# sensors.net
KiCad netlist of a schematic drawn in Altium Designer
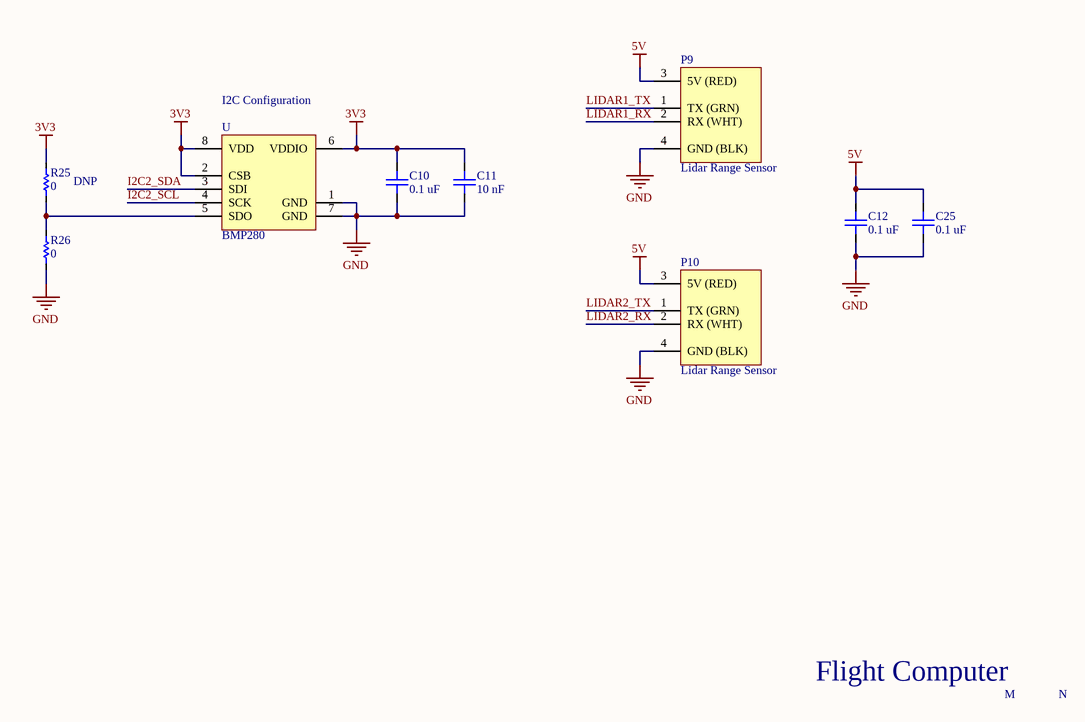
[diagram p0: sensors.SchDoc]

(export (version "E")
  (design (tool "Eeschema 10.0.6"))
  (components
    (comp (ref "C10")
      (value "0.1 uF")
      (footprint "CAP-CER-0805-SHORT")
      (description "±10%, 0805")
      (libsource (lib "passive") (part "CAP-CER-0.1uF-25V"))
    )
    (comp (ref "C11")
      (value "10 nF")
      (footprint "CAP-CER-0805-SHORT")
      (description "±10%, 0805")
      (libsource (lib "passive") (part "CAP-CER-10nF-50V"))
    )
    (comp (ref "C12")
      (value "0.1 uF")
      (footprint "CAP-CER-0805-SHORT")
      (description "±10%, 0805")
      (libsource (lib "passive") (part "CAP-CER-0.1uF-25V"))
    )
    (comp (ref "C25")
      (value "0.1 uF")
      (footprint "CAP-CER-0805-SHORT")
      (description "±10%, 0805")
      (libsource (lib "passive") (part "CAP-CER-0.1uF-25V"))
    )
    (comp (ref "P9")
      (value "Lidar Range Sensor")
      (footprint "4x1 Shrouded Header 1.25mm")
      (libsource (lib "connector") (part "Lidar Range Sensor"))
    )
    (comp (ref "P10")
      (value "Lidar Range Sensor")
      (footprint "4x1 Shrouded Header 1.25mm")
      (libsource (lib "connector") (part "Lidar Range Sensor"))
    )
    (comp (ref "R25")
      (value "0")
      (footprint "RES-0805")
      (description "0805")
      (libsource (lib "passive") (part "RES-0-1/8W"))
    )
    (comp (ref "R26")
      (value "0")
      (footprint "RES-0805")
      (description "0805")
      (libsource (lib "passive") (part "RES-0-1/8W"))
    )
    (comp (ref "U")
      (value "BMP280")
      (footprint "LGA8")
      (description "Digital Pressure Sensor")
      (libsource (lib "ic") (part "BMP280"))
    )
  )
  (nets
    (net (code "1") (name "/I2C2_SCL") (class "Default")
      (node (ref "U") (pin "4") (pinfunction "SCK_4") (pintype "passive"))
    )
    (net (code "2") (name "/I2C2_SDA") (class "Default")
      (node (ref "U") (pin "3") (pinfunction "SDI_3") (pintype "passive"))
    )
    (net (code "3") (name "/LIDAR1_RX") (class "Default")
      (node (ref "P9") (pin "2") (pinfunction "RX_(WHT)_2") (pintype "passive"))
    )
    (net (code "4") (name "/LIDAR1_TX") (class "Default")
      (node (ref "P9") (pin "1") (pinfunction "TX_(GRN)_1") (pintype "passive"))
    )
    (net (code "5") (name "/LIDAR2_RX") (class "Default")
      (node (ref "P10") (pin "2") (pinfunction "RX_(WHT)_2") (pintype "passive"))
    )
    (net (code "6") (name "/LIDAR2_TX") (class "Default")
      (node (ref "P10") (pin "1") (pinfunction "TX_(GRN)_1") (pintype "passive"))
    )
    (net (code "7") (name "3V3") (class "Default")
      (node (ref "C10") (pin "2") (pinfunction "2_2") (pintype "passive"))
      (node (ref "C11") (pin "2") (pinfunction "2_2") (pintype "passive"))
      (node (ref "R25") (pin "2") (pinfunction "2_2") (pintype "passive"))
      (node (ref "U") (pin "2") (pinfunction "CSB_2") (pintype "passive"))
      (node (ref "U") (pin "6") (pinfunction "VDDIO_6") (pintype "passive"))
      (node (ref "U") (pin "8") (pinfunction "VDD_8") (pintype "passive"))
    )
    (net (code "8") (name "5V") (class "Default")
      (node (ref "C12") (pin "2") (pinfunction "2_2") (pintype "passive"))
      (node (ref "C25") (pin "2") (pinfunction "2_2") (pintype "passive"))
      (node (ref "P10") (pin "3") (pinfunction "5V_(RED)_3") (pintype "passive"))
      (node (ref "P9") (pin "3") (pinfunction "5V_(RED)_3") (pintype "passive"))
    )
    (net (code "9") (name "GND") (class "Default")
      (node (ref "C10") (pin "1") (pinfunction "1_1") (pintype "passive"))
      (node (ref "C11") (pin "1") (pinfunction "1_1") (pintype "passive"))
      (node (ref "C12") (pin "1") (pinfunction "1_1") (pintype "passive"))
      (node (ref "C25") (pin "1") (pinfunction "1_1") (pintype "passive"))
      (node (ref "P10") (pin "4") (pinfunction "GND_(BLK)_4") (pintype "passive"))
      (node (ref "P9") (pin "4") (pinfunction "GND_(BLK)_4") (pintype "passive"))
      (node (ref "R26") (pin "1") (pinfunction "1_1") (pintype "passive"))
      (node (ref "U") (pin "1") (pinfunction "GND_1") (pintype "passive"))
      (node (ref "U") (pin "7") (pinfunction "GND_7") (pintype "passive"))
    )
    (net (code "10") (name "Net-(U-SDO)") (class "Default")
      (node (ref "R25") (pin "1") (pinfunction "1_1") (pintype "passive"))
      (node (ref "R26") (pin "2") (pinfunction "2_2") (pintype "passive"))
      (node (ref "U") (pin "5") (pinfunction "SDO_5") (pintype "passive"))
    )
  )
)
